# Board_lengkap.net
KiCad netlist of a schematic drawn in EAGLE
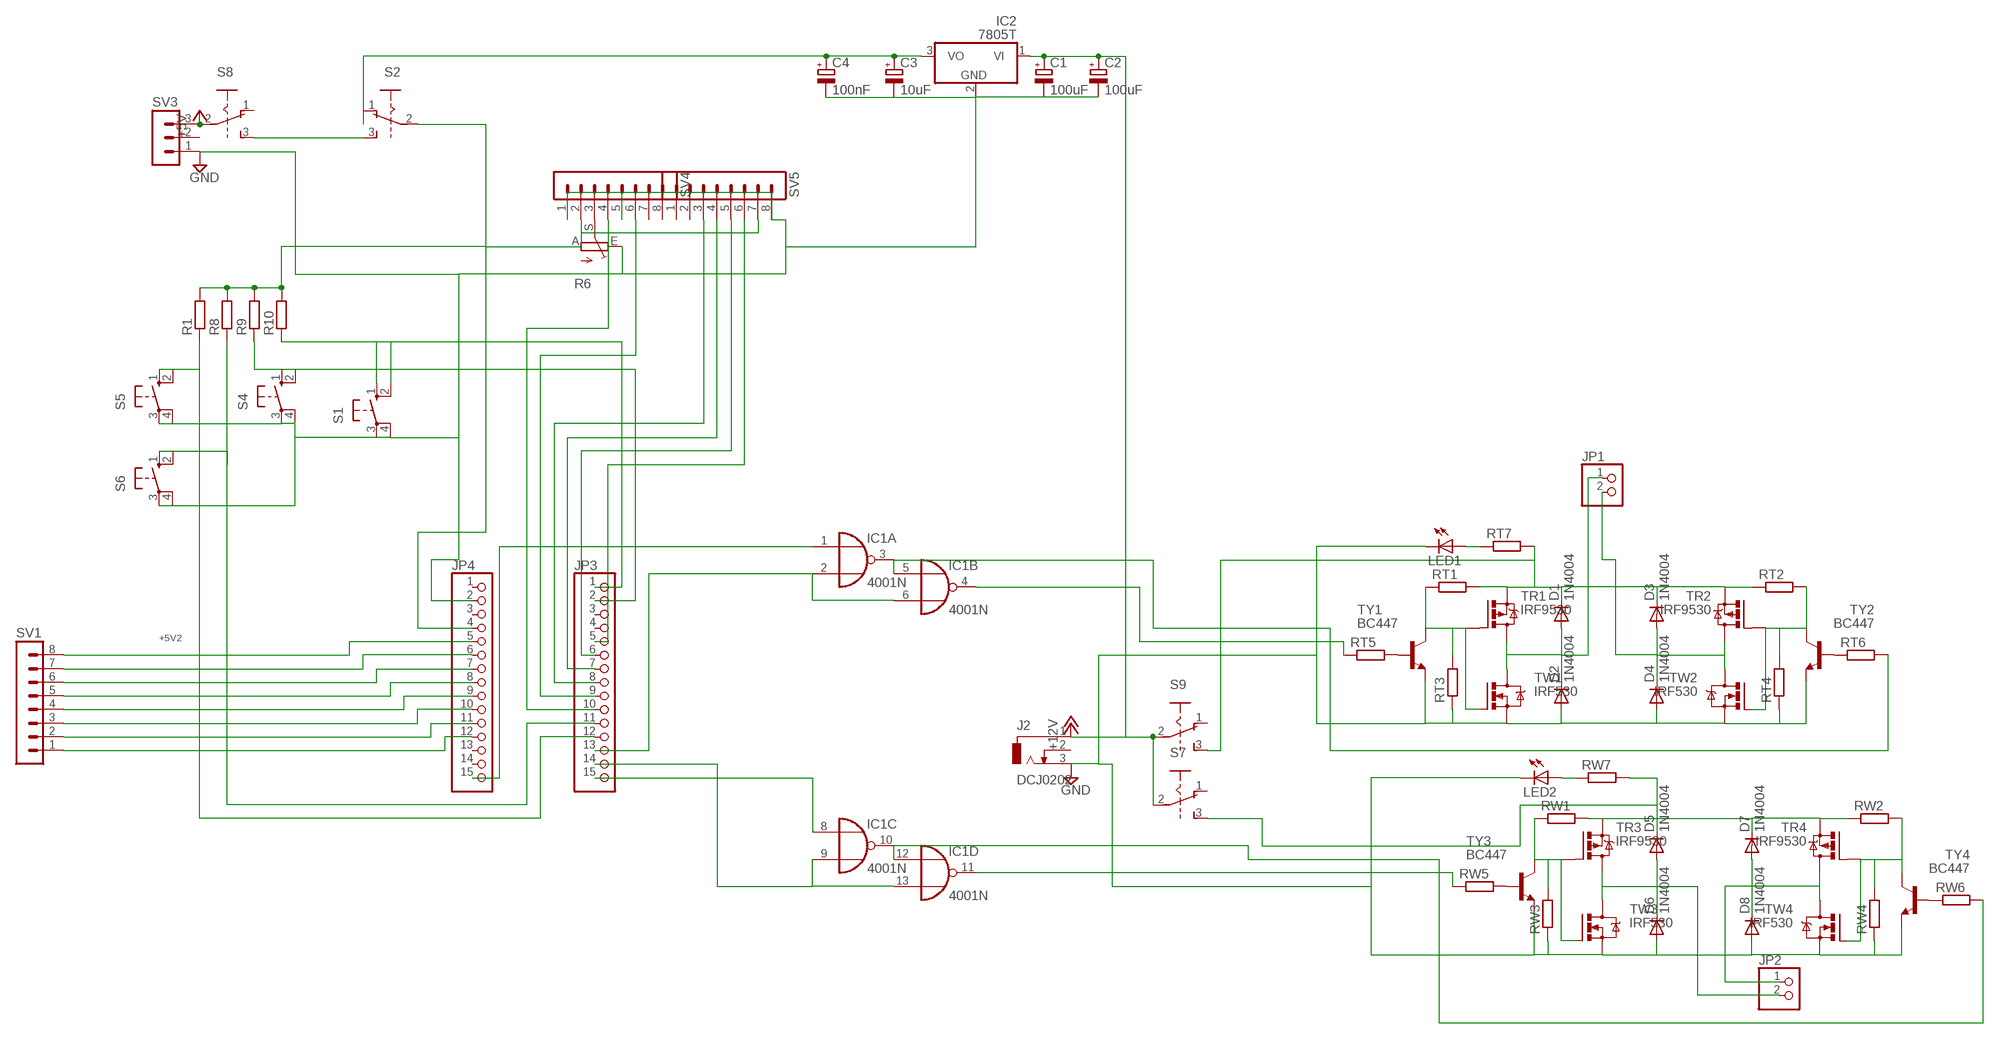
[diagram p0: schematic, sheet 1]
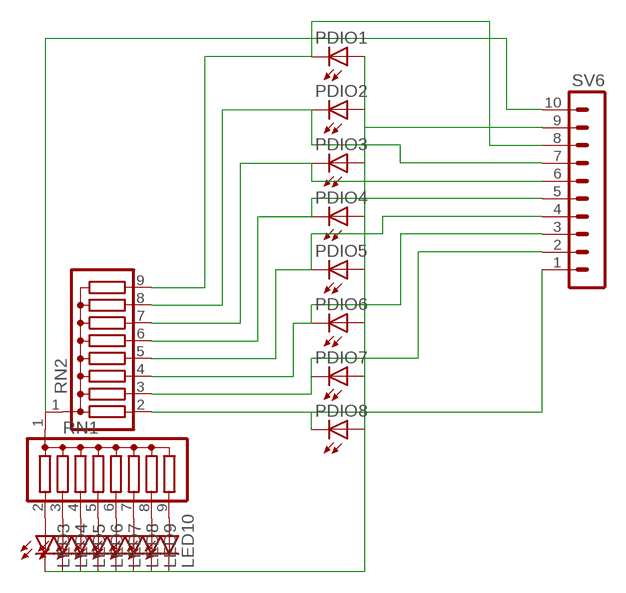
[diagram p1: schematic, sheet 2]

(export (version "E")
  (design (tool "Eeschema 10.0.6"))
  (components
    (comp (ref "LED3")
      (value "LED3MM")
      (footprint "eagle-import:LED3MM")
      (libsource (lib "eagle-import") (part "LED3MM"))
    )
    (comp (ref "LED4")
      (value "LED3MM")
      (footprint "eagle-import:LED3MM")
      (libsource (lib "eagle-import") (part "LED3MM"))
    )
    (comp (ref "LED5")
      (value "LED3MM")
      (footprint "eagle-import:LED3MM")
      (libsource (lib "eagle-import") (part "LED3MM"))
    )
    (comp (ref "LED6")
      (value "LED3MM")
      (footprint "eagle-import:LED3MM")
      (libsource (lib "eagle-import") (part "LED3MM"))
    )
    (comp (ref "LED7")
      (value "LED3MM")
      (footprint "eagle-import:LED3MM")
      (libsource (lib "eagle-import") (part "LED3MM"))
    )
    (comp (ref "LED8")
      (value "LED3MM")
      (footprint "eagle-import:LED3MM")
      (libsource (lib "eagle-import") (part "LED3MM"))
    )
    (comp (ref "LED9")
      (value "LED3MM")
      (footprint "eagle-import:LED3MM")
      (libsource (lib "eagle-import") (part "LED3MM"))
    )
    (comp (ref "LED10")
      (value "LED3MM")
      (footprint "eagle-import:LED3MM")
      (libsource (lib "eagle-import") (part "LED3MM"))
    )
    (comp (ref "PDIO1")
      (value "LED3MM")
      (footprint "eagle-import:LED3MM")
      (libsource (lib "eagle-import") (part "LED3MM"))
    )
    (comp (ref "PDIO2")
      (value "LED3MM")
      (footprint "eagle-import:LED3MM")
      (libsource (lib "eagle-import") (part "LED3MM"))
    )
    (comp (ref "PDIO3")
      (value "LED3MM")
      (footprint "eagle-import:LED3MM")
      (libsource (lib "eagle-import") (part "LED3MM"))
    )
    (comp (ref "PDIO4")
      (value "LED3MM")
      (footprint "eagle-import:LED3MM")
      (libsource (lib "eagle-import") (part "LED3MM"))
    )
    (comp (ref "PDIO5")
      (value "LED3MM")
      (footprint "eagle-import:LED3MM")
      (libsource (lib "eagle-import") (part "LED3MM"))
    )
    (comp (ref "PDIO6")
      (value "LED3MM")
      (footprint "eagle-import:LED3MM")
      (libsource (lib "eagle-import") (part "LED3MM"))
    )
    (comp (ref "PDIO7")
      (value "LED3MM")
      (footprint "eagle-import:LED3MM")
      (libsource (lib "eagle-import") (part "LED3MM"))
    )
    (comp (ref "PDIO8")
      (value "LED3MM")
      (footprint "eagle-import:LED3MM")
      (libsource (lib "eagle-import") (part "LED3MM"))
    )
    (comp (ref "RN1")
      (value "G08R")
      (footprint "eagle-import:SIL9")
      (libsource (lib "eagle-import") (part "G08R"))
    )
    (comp (ref "RN2")
      (value "G08R")
      (footprint "eagle-import:SIL9")
      (libsource (lib "eagle-import") (part "G08R"))
    )
    (comp (ref "SV6")
      (value "MA10-1")
      (footprint "eagle-import:MA10-1")
      (libsource (lib "eagle-import") (part "MA10-1"))
    )
    (comp (ref "C1")
      (value "100uF")
      (footprint "eagle-import:E2,5-6")
      (libsource (lib "eagle-import") (part "CPOL-EUE2.5-6"))
    )
    (comp (ref "C2")
      (value "100uF")
      (footprint "eagle-import:E2,5-6")
      (libsource (lib "eagle-import") (part "CPOL-EUE2.5-6"))
    )
    (comp (ref "C3")
      (value "10uF")
      (footprint "eagle-import:E2,5-6")
      (libsource (lib "eagle-import") (part "CPOL-EUE2.5-6"))
    )
    (comp (ref "C4")
      (value "100nF")
      (footprint "eagle-import:E2,5-6")
      (libsource (lib "eagle-import") (part "CPOL-EUE2.5-6"))
    )
    (comp (ref "D1")
      (value "1N4004")
      (footprint "eagle-import:DO41-10")
      (libsource (lib "eagle-import") (part "1N4004"))
    )
    (comp (ref "D2")
      (value "1N4004")
      (footprint "eagle-import:DO41-10")
      (libsource (lib "eagle-import") (part "1N4004"))
    )
    (comp (ref "D3")
      (value "1N4004")
      (footprint "eagle-import:DO41-10")
      (libsource (lib "eagle-import") (part "1N4004"))
    )
    (comp (ref "D4")
      (value "1N4004")
      (footprint "eagle-import:DO41-10")
      (libsource (lib "eagle-import") (part "1N4004"))
    )
    (comp (ref "D5")
      (value "1N4004")
      (footprint "eagle-import:DO41-10")
      (libsource (lib "eagle-import") (part "1N4004"))
    )
    (comp (ref "D6")
      (value "1N4004")
      (footprint "eagle-import:DO41-10")
      (libsource (lib "eagle-import") (part "1N4004"))
    )
    (comp (ref "D7")
      (value "1N4004")
      (footprint "eagle-import:DO41-10")
      (libsource (lib "eagle-import") (part "1N4004"))
    )
    (comp (ref "D8")
      (value "1N4004")
      (footprint "eagle-import:DO41-10")
      (libsource (lib "eagle-import") (part "1N4004"))
    )
    (comp (ref "IC1")
      (value "4001N")
      (footprint "eagle-import:DIL14")
      (libsource (lib "eagle-import") (part "4001N"))
    )
    (comp (ref "IC2")
      (value "7805T")
      (footprint "eagle-import:TO220H")
      (libsource (lib "eagle-import") (part "78T05"))
    )
    (comp (ref "J2")
      (value "DCJ0202")
      (footprint "eagle-import:DCJ0202")
      (libsource (lib "eagle-import") (part "DCJ0202"))
    )
    (comp (ref "JP1")
      (value "PINHD-1X2")
      (footprint "eagle-import:1X02")
      (libsource (lib "eagle-import") (part "PINHD-1X2"))
    )
    (comp (ref "JP2")
      (value "PINHD-1X2")
      (footprint "eagle-import:1X02")
      (libsource (lib "eagle-import") (part "PINHD-1X2"))
    )
    (comp (ref "JP3")
      (value "PINHD-1X15")
      (footprint "eagle-import:1X15")
      (libsource (lib "eagle-import") (part "PINHD-1X15"))
    )
    (comp (ref "JP4")
      (value "PINHD-1X15")
      (footprint "eagle-import:1X15")
      (libsource (lib "eagle-import") (part "PINHD-1X15"))
    )
    (comp (ref "LED1")
      (value "LED5MM")
      (footprint "eagle-import:LED5MM")
      (libsource (lib "eagle-import") (part "LED5MM"))
    )
    (comp (ref "LED2")
      (value "LED5MM")
      (footprint "eagle-import:LED5MM")
      (libsource (lib "eagle-import") (part "LED5MM"))
    )
    (comp (ref "R1")
      (value "R-EU_0204/7")
      (footprint "eagle-import:0204_7")
      (libsource (lib "eagle-import") (part "R-EU_0204/7"))
    )
    (comp (ref "R6")
      (value "TRIM_EU-B25P")
      (footprint "eagle-import:B25P")
      (libsource (lib "eagle-import") (part "TRIM_EU-B25P"))
    )
    (comp (ref "R8")
      (value "R-EU_0204/7")
      (footprint "eagle-import:0204_7")
      (libsource (lib "eagle-import") (part "R-EU_0204/7"))
    )
    (comp (ref "R9")
      (value "R-EU_0204/7")
      (footprint "eagle-import:0204_7")
      (libsource (lib "eagle-import") (part "R-EU_0204/7"))
    )
    (comp (ref "R10")
      (value "R-EU_0204/7")
      (footprint "eagle-import:0204_7")
      (libsource (lib "eagle-import") (part "R-EU_0204/7"))
    )
    (comp (ref "RT1")
      (value "R-EU_0207/7")
      (footprint "eagle-import:0207_7")
      (libsource (lib "eagle-import") (part "R-EU_0207/7"))
    )
    (comp (ref "RT2")
      (value "R-EU_0207/7")
      (footprint "eagle-import:0207_7")
      (libsource (lib "eagle-import") (part "R-EU_0207/7"))
    )
    (comp (ref "RT3")
      (value "R-EU_0207/7")
      (footprint "eagle-import:0207_7")
      (libsource (lib "eagle-import") (part "R-EU_0207/7"))
    )
    (comp (ref "RT4")
      (value "R-EU_0207/7")
      (footprint "eagle-import:0207_7")
      (libsource (lib "eagle-import") (part "R-EU_0207/7"))
    )
    (comp (ref "RT5")
      (value "R-EU_0207/7")
      (footprint "eagle-import:0207_7")
      (libsource (lib "eagle-import") (part "R-EU_0207/7"))
    )
    (comp (ref "RT6")
      (value "R-EU_0207/7")
      (footprint "eagle-import:0207_7")
      (libsource (lib "eagle-import") (part "R-EU_0207/7"))
    )
    (comp (ref "RT7")
      (value "R-EU_0207/7")
      (footprint "eagle-import:0207_7")
      (libsource (lib "eagle-import") (part "R-EU_0207/7"))
    )
    (comp (ref "RW1")
      (value "R-EU_0207/7")
      (footprint "eagle-import:0207_7")
      (libsource (lib "eagle-import") (part "R-EU_0207/7"))
    )
    (comp (ref "RW2")
      (value "R-EU_0207/7")
      (footprint "eagle-import:0207_7")
      (libsource (lib "eagle-import") (part "R-EU_0207/7"))
    )
    (comp (ref "RW3")
      (value "R-EU_0207/7")
      (footprint "eagle-import:0207_7")
      (libsource (lib "eagle-import") (part "R-EU_0207/7"))
    )
    (comp (ref "RW4")
      (value "R-EU_0207/7")
      (footprint "eagle-import:0207_7")
      (libsource (lib "eagle-import") (part "R-EU_0207/7"))
    )
    (comp (ref "RW5")
      (value "R-EU_0207/7")
      (footprint "eagle-import:0207_7")
      (libsource (lib "eagle-import") (part "R-EU_0207/7"))
    )
    (comp (ref "RW6")
      (value "R-EU_0207/7")
      (footprint "eagle-import:0207_7")
      (libsource (lib "eagle-import") (part "R-EU_0207/7"))
    )
    (comp (ref "RW7")
      (value "R-EU_0207/7")
      (footprint "eagle-import:0207_7")
      (libsource (lib "eagle-import") (part "R-EU_0207/7"))
    )
    (comp (ref "S1")
      (value "10-XX")
      (footprint "eagle-import:B3F-10XX")
      (libsource (lib "eagle-import") (part "10-XX"))
    )
    (comp (ref "S2")
      (value "A68-A31")
      (footprint "eagle-import:A68-A31")
      (libsource (lib "eagle-import") (part "A68-A31"))
    )
    (comp (ref "S4")
      (value "10-XX")
      (footprint "eagle-import:B3F-10XX")
      (libsource (lib "eagle-import") (part "10-XX"))
    )
    (comp (ref "S5")
      (value "10-XX")
      (footprint "eagle-import:B3F-10XX")
      (libsource (lib "eagle-import") (part "10-XX"))
    )
    (comp (ref "S6")
      (value "10-XX")
      (footprint "eagle-import:B3F-10XX")
      (libsource (lib "eagle-import") (part "10-XX"))
    )
    (comp (ref "S7")
      (value "A68-A31")
      (footprint "eagle-import:A68-A31")
      (libsource (lib "eagle-import") (part "A68-A31"))
    )
    (comp (ref "S8")
      (value "A68-A31")
      (footprint "eagle-import:A68-A31")
      (libsource (lib "eagle-import") (part "A68-A31"))
    )
    (comp (ref "S9")
      (value "A68-A31")
      (footprint "eagle-import:A68-A31")
      (libsource (lib "eagle-import") (part "A68-A31"))
    )
    (comp (ref "SV1")
      (value "MA08-1")
      (footprint "eagle-import:MA08-1")
      (libsource (lib "eagle-import") (part "MA08-1"))
    )
    (comp (ref "SV3")
      (value "MA03-1")
      (footprint "eagle-import:MA03-1")
      (libsource (lib "eagle-import") (part "MA03-1"))
    )
    (comp (ref "SV4")
      (value "MA08-1")
      (footprint "eagle-import:MA08-1")
      (libsource (lib "eagle-import") (part "MA08-1"))
    )
    (comp (ref "SV5")
      (value "MA08-1")
      (footprint "eagle-import:MA08-1")
      (libsource (lib "eagle-import") (part "MA08-1"))
    )
    (comp (ref "TR1")
      (value "IRF9530")
      (footprint "eagle-import:TO220BV")
      (libsource (lib "eagle-import") (part "IRF9530"))
    )
    (comp (ref "TR2")
      (value "IRF9530")
      (footprint "eagle-import:TO220BV")
      (libsource (lib "eagle-import") (part "IRF9530"))
    )
    (comp (ref "TR3")
      (value "IRF9530")
      (footprint "eagle-import:TO220BV")
      (libsource (lib "eagle-import") (part "IRF9530"))
    )
    (comp (ref "TR4")
      (value "IRF9530")
      (footprint "eagle-import:TO220BV")
      (libsource (lib "eagle-import") (part "IRF9530"))
    )
    (comp (ref "TW1")
      (value "IRF530")
      (footprint "eagle-import:TO220BV")
      (libsource (lib "eagle-import") (part "IRF530"))
    )
    (comp (ref "TW2")
      (value "IRF530")
      (footprint "eagle-import:TO220BV")
      (libsource (lib "eagle-import") (part "IRF530"))
    )
    (comp (ref "TW3")
      (value "IRF530")
      (footprint "eagle-import:TO220BV")
      (libsource (lib "eagle-import") (part "IRF530"))
    )
    (comp (ref "TW4")
      (value "IRF530")
      (footprint "eagle-import:TO220BV")
      (libsource (lib "eagle-import") (part "IRF530"))
    )
    (comp (ref "TY1")
      (value "BC447")
      (footprint "eagle-import:TO92-EBC")
      (libsource (lib "eagle-import") (part "BC447"))
    )
    (comp (ref "TY2")
      (value "BC447")
      (footprint "eagle-import:TO92-EBC")
      (libsource (lib "eagle-import") (part "BC447"))
    )
    (comp (ref "TY3")
      (value "BC447")
      (footprint "eagle-import:TO92-EBC")
      (libsource (lib "eagle-import") (part "BC447"))
    )
    (comp (ref "TY4")
      (value "BC447")
      (footprint "eagle-import:TO92-EBC")
      (libsource (lib "eagle-import") (part "BC447"))
    )
  )
  (nets
    (net (code "1") (name "+5V") (class "Default")
      (node (ref "S8") (pin "2") (pinfunction "P_2") (pintype "passive"))
      (node (ref "SV3") (pin "3") (pinfunction "3_3") (pintype "passive"))
    )
    (net (code "2") (name "+5V2") (class "Default")
      (node (ref "JP4") (pin "4") (pinfunction "4_4") (pintype "passive"))
      (node (ref "R1") (pin "2") (pinfunction "2_2") (pintype "passive"))
      (node (ref "R10") (pin "2") (pinfunction "2_2") (pintype "passive"))
      (node (ref "R6") (pin "A") (pinfunction "A_A") (pintype "passive"))
      (node (ref "R8") (pin "2") (pinfunction "2_2") (pintype "passive"))
      (node (ref "R9") (pin "2") (pinfunction "2_2") (pintype "passive"))
      (node (ref "S2") (pin "2") (pinfunction "P_2") (pintype "passive"))
      (node (ref "SV4") (pin "2") (pinfunction "2_2") (pintype "passive"))
      (node (ref "SV5") (pin "7") (pinfunction "7_7") (pintype "passive"))
    )
    (net (code "3") (name "+12V") (class "Default")
      (node (ref "C1") (pin "+") (pinfunction "+_+") (pintype "passive"))
      (node (ref "C2") (pin "+") (pinfunction "+_+") (pintype "passive"))
      (node (ref "IC2") (pin "1") (pinfunction "VI_1") (pintype "input"))
      (node (ref "J2") (pin "1") (pinfunction "1_1") (pintype "passive"))
      (node (ref "S7") (pin "2") (pinfunction "P_2") (pintype "passive"))
      (node (ref "S9") (pin "2") (pinfunction "P_2") (pintype "passive"))
    )
    (net (code "4") (name "GND") (class "Default")
      (node (ref "C1") (pin "-") (pinfunction "-_-") (pintype "passive"))
      (node (ref "C2") (pin "-") (pinfunction "-_-") (pintype "passive"))
      (node (ref "C3") (pin "-") (pinfunction "-_-") (pintype "passive"))
      (node (ref "C4") (pin "-") (pinfunction "-_-") (pintype "passive"))
      (node (ref "D2") (pin "A") (pinfunction "A_A") (pintype "passive"))
      (node (ref "D4") (pin "A") (pinfunction "A_A") (pintype "passive"))
      (node (ref "D6") (pin "A") (pinfunction "A_A") (pintype "passive"))
      (node (ref "D8") (pin "A") (pinfunction "A_A") (pintype "passive"))
      (node (ref "IC2") (pin "2") (pinfunction "GND_2") (pintype "passive"))
      (node (ref "J2") (pin "3") (pinfunction "3_3") (pintype "passive"))
      (node (ref "JP4") (pin "2") (pinfunction "2_2") (pintype "passive"))
      (node (ref "LED1") (pin "K") (pinfunction "C_K") (pintype "passive"))
      (node (ref "LED2") (pin "K") (pinfunction "C_K") (pintype "passive"))
      (node (ref "R6") (pin "E") (pinfunction "E_E") (pintype "passive"))
      (node (ref "RT3") (pin "1") (pinfunction "1_1") (pintype "passive"))
      (node (ref "RT4") (pin "1") (pinfunction "1_1") (pintype "passive"))
      (node (ref "RW3") (pin "1") (pinfunction "1_1") (pintype "passive"))
      (node (ref "RW4") (pin "1") (pinfunction "1_1") (pintype "passive"))
      (node (ref "S1") (pin "3") (pinfunction "P_3") (pintype "passive"))
      (node (ref "S1") (pin "4") (pinfunction "P1_4") (pintype "passive"))
      (node (ref "S4") (pin "3") (pinfunction "P_3") (pintype "passive"))
      (node (ref "S4") (pin "4") (pinfunction "P1_4") (pintype "passive"))
      (node (ref "S5") (pin "3") (pinfunction "P_3") (pintype "passive"))
      (node (ref "S5") (pin "4") (pinfunction "P1_4") (pintype "passive"))
      (node (ref "S6") (pin "3") (pinfunction "P_3") (pintype "passive"))
      (node (ref "S6") (pin "4") (pinfunction "P1_4") (pintype "passive"))
      (node (ref "SV3") (pin "1") (pinfunction "1_1") (pintype "passive"))
      (node (ref "SV4") (pin "1") (pinfunction "1_1") (pintype "passive"))
      (node (ref "SV4") (pin "5") (pinfunction "5_5") (pintype "passive"))
      (node (ref "SV5") (pin "8") (pinfunction "8_8") (pintype "passive"))
      (node (ref "TW1") (pin "S") (pinfunction "S_S") (pintype "passive"))
      (node (ref "TW2") (pin "S") (pinfunction "S_S") (pintype "passive"))
      (node (ref "TW3") (pin "S") (pinfunction "S_S") (pintype "passive"))
      (node (ref "TW4") (pin "S") (pinfunction "S_S") (pintype "passive"))
      (node (ref "TY1") (pin "E") (pinfunction "E_E") (pintype "passive"))
      (node (ref "TY2") (pin "E") (pinfunction "E_E") (pintype "passive"))
      (node (ref "TY3") (pin "E") (pinfunction "E_E") (pintype "passive"))
      (node (ref "TY4") (pin "E") (pinfunction "E_E") (pintype "passive"))
    )
    (net (code "5") (name "Net-(D1-PadA)") (class "Default")
      (node (ref "D1") (pin "A") (pinfunction "A_A") (pintype "passive"))
      (node (ref "D2") (pin "C") (pinfunction "C_C") (pintype "passive"))
      (node (ref "JP1") (pin "1") (pinfunction "1_1") (pintype "passive"))
      (node (ref "TR1") (pin "D") (pinfunction "D_D") (pintype "passive"))
      (node (ref "TW1") (pin "D") (pinfunction "D_D") (pintype "passive"))
    )
    (net (code "6") (name "Net-(D3-PadA)") (class "Default")
      (node (ref "D3") (pin "A") (pinfunction "A_A") (pintype "passive"))
      (node (ref "D4") (pin "C") (pinfunction "C_C") (pintype "passive"))
      (node (ref "JP1") (pin "2") (pinfunction "2_2") (pintype "passive"))
      (node (ref "TR2") (pin "D") (pinfunction "D_D") (pintype "passive"))
      (node (ref "TW2") (pin "D") (pinfunction "D_D") (pintype "passive"))
    )
    (net (code "7") (name "Net-(D5-PadA)") (class "Default")
      (node (ref "D5") (pin "A") (pinfunction "A_A") (pintype "passive"))
      (node (ref "D6") (pin "C") (pinfunction "C_C") (pintype "passive"))
      (node (ref "JP2") (pin "2") (pinfunction "2_2") (pintype "passive"))
      (node (ref "TR3") (pin "D") (pinfunction "D_D") (pintype "passive"))
      (node (ref "TW3") (pin "D") (pinfunction "D_D") (pintype "passive"))
    )
    (net (code "8") (name "Net-(D7-PadA)") (class "Default")
      (node (ref "D7") (pin "A") (pinfunction "A_A") (pintype "passive"))
      (node (ref "D8") (pin "C") (pinfunction "C_C") (pintype "passive"))
      (node (ref "JP2") (pin "1") (pinfunction "1_1") (pintype "passive"))
      (node (ref "TR4") (pin "D") (pinfunction "D_D") (pintype "passive"))
      (node (ref "TW4") (pin "D") (pinfunction "D_D") (pintype "passive"))
    )
    (net (code "9") (name "Net-(IC1A-I0)") (class "Default")
      (node (ref "IC1") (pin "1") (pinfunction "I0_1") (pintype "input"))
      (node (ref "JP4") (pin "15") (pinfunction "15_15") (pintype "passive"))
    )
    (net (code "10") (name "Net-(IC1A-I1)") (class "Default")
      (node (ref "IC1") (pin "2") (pinfunction "I1_2") (pintype "input"))
      (node (ref "IC1") (pin "6") (pinfunction "I1_6") (pintype "input"))
      (node (ref "JP3") (pin "13") (pinfunction "13_13") (pintype "passive"))
    )
    (net (code "11") (name "Net-(IC1A-O)") (class "Default")
      (node (ref "IC1") (pin "3") (pinfunction "O_3") (pintype "output"))
      (node (ref "IC1") (pin "5") (pinfunction "I0_5") (pintype "input"))
      (node (ref "RT6") (pin "2") (pinfunction "2_2") (pintype "passive"))
    )
    (net (code "12") (name "Net-(IC1B-O)") (class "Default")
      (node (ref "IC1") (pin "4") (pinfunction "O_4") (pintype "output"))
      (node (ref "RT5") (pin "1") (pinfunction "1_1") (pintype "passive"))
    )
    (net (code "13") (name "Net-(IC1C-I0)") (class "Default")
      (node (ref "IC1") (pin "8") (pinfunction "I0_8") (pintype "input"))
      (node (ref "JP3") (pin "15") (pinfunction "15_15") (pintype "passive"))
    )
    (net (code "14") (name "Net-(IC1C-I1)") (class "Default")
      (node (ref "IC1") (pin "13") (pinfunction "I1_13") (pintype "input"))
      (node (ref "IC1") (pin "9") (pinfunction "I1_9") (pintype "input"))
      (node (ref "JP3") (pin "14") (pinfunction "14_14") (pintype "passive"))
    )
    (net (code "15") (name "Net-(IC1C-O)") (class "Default")
      (node (ref "IC1") (pin "10") (pinfunction "O_10") (pintype "output"))
      (node (ref "IC1") (pin "12") (pinfunction "I0_12") (pintype "input"))
      (node (ref "RW6") (pin "2") (pinfunction "2_2") (pintype "passive"))
    )
    (net (code "16") (name "Net-(IC1D-O)") (class "Default")
      (node (ref "IC1") (pin "11") (pinfunction "O_11") (pintype "output"))
      (node (ref "RW5") (pin "1") (pinfunction "1_1") (pintype "passive"))
    )
    (net (code "17") (name "Net-(IC2-VO)") (class "Default")
      (node (ref "C3") (pin "+") (pinfunction "+_+") (pintype "passive"))
      (node (ref "C4") (pin "+") (pinfunction "+_+") (pintype "passive"))
      (node (ref "IC2") (pin "3") (pinfunction "VO_3") (pintype "passive"))
    )
    (net (code "18") (name "Net-(JP3-Pad5)") (class "Default")
      (node (ref "JP3") (pin "5") (pinfunction "5_5") (pintype "passive"))
      (node (ref "SV5") (pin "6") (pinfunction "6_6") (pintype "passive"))
    )
    (net (code "19") (name "Net-(JP3-Pad6)") (class "Default")
      (node (ref "JP3") (pin "6") (pinfunction "6_6") (pintype "passive"))
      (node (ref "SV5") (pin "5") (pinfunction "5_5") (pintype "passive"))
    )
    (net (code "20") (name "Net-(JP3-Pad7)") (class "Default")
      (node (ref "JP3") (pin "7") (pinfunction "7_7") (pintype "passive"))
      (node (ref "SV5") (pin "4") (pinfunction "4_4") (pintype "passive"))
    )
    (net (code "21") (name "Net-(JP3-Pad8)") (class "Default")
      (node (ref "JP3") (pin "8") (pinfunction "8_8") (pintype "passive"))
      (node (ref "SV5") (pin "3") (pinfunction "3_3") (pintype "passive"))
    )
    (net (code "22") (name "Net-(JP3-Pad9)") (class "Default")
      (node (ref "JP3") (pin "9") (pinfunction "9_9") (pintype "passive"))
      (node (ref "SV4") (pin "6") (pinfunction "6_6") (pintype "passive"))
    )
    (net (code "23") (name "Net-(JP3-Pad10)") (class "Default")
      (node (ref "JP3") (pin "10") (pinfunction "10_10") (pintype "passive"))
      (node (ref "SV4") (pin "4") (pinfunction "4_4") (pintype "passive"))
    )
    (net (code "24") (name "Net-(JP4-Pad5)") (class "Default")
      (node (ref "JP4") (pin "5") (pinfunction "5_5") (pintype "passive"))
      (node (ref "SV1") (pin "8") (pinfunction "8_8") (pintype "passive"))
    )
    (net (code "25") (name "Net-(JP4-Pad6)") (class "Default")
      (node (ref "JP4") (pin "6") (pinfunction "6_6") (pintype "passive"))
      (node (ref "SV1") (pin "7") (pinfunction "7_7") (pintype "passive"))
    )
    (net (code "26") (name "Net-(JP4-Pad7)") (class "Default")
      (node (ref "JP4") (pin "7") (pinfunction "7_7") (pintype "passive"))
      (node (ref "SV1") (pin "6") (pinfunction "6_6") (pintype "passive"))
    )
    (net (code "27") (name "Net-(JP4-Pad8)") (class "Default")
      (node (ref "JP4") (pin "8") (pinfunction "8_8") (pintype "passive"))
      (node (ref "SV1") (pin "5") (pinfunction "5_5") (pintype "passive"))
    )
    (net (code "28") (name "Net-(JP4-Pad9)") (class "Default")
      (node (ref "JP4") (pin "9") (pinfunction "9_9") (pintype "passive"))
      (node (ref "SV1") (pin "4") (pinfunction "4_4") (pintype "passive"))
    )
    (net (code "29") (name "Net-(JP4-Pad10)") (class "Default")
      (node (ref "JP4") (pin "10") (pinfunction "10_10") (pintype "passive"))
      (node (ref "SV1") (pin "3") (pinfunction "3_3") (pintype "passive"))
    )
    (net (code "30") (name "Net-(JP4-Pad11)") (class "Default")
      (node (ref "JP4") (pin "11") (pinfunction "11_11") (pintype "passive"))
      (node (ref "SV1") (pin "2") (pinfunction "2_2") (pintype "passive"))
    )
    (net (code "31") (name "Net-(JP4-Pad12)") (class "Default")
      (node (ref "JP4") (pin "12") (pinfunction "12_12") (pintype "passive"))
      (node (ref "SV1") (pin "1") (pinfunction "1_1") (pintype "passive"))
    )
    (net (code "32") (name "Net-(LED1-PadA)") (class "Default")
      (node (ref "LED1") (pin "A") (pinfunction "A_A") (pintype "passive"))
      (node (ref "RT7") (pin "1") (pinfunction "1_1") (pintype "passive"))
    )
    (net (code "33") (name "Net-(LED2-PadA)") (class "Default")
      (node (ref "LED2") (pin "A") (pinfunction "A_A") (pintype "passive"))
      (node (ref "RW7") (pin "1") (pinfunction "1_1") (pintype "passive"))
    )
    (net (code "34") (name "Net-(LED3-PadA)") (class "Default")
      (node (ref "LED3") (pin "A") (pinfunction "A_A") (pintype "passive"))
      (node (ref "RN1") (pin "2") (pinfunction "2_2") (pintype "passive"))
    )
    (net (code "35") (name "Net-(LED4-PadA)") (class "Default")
      (node (ref "LED4") (pin "A") (pinfunction "A_A") (pintype "passive"))
      (node (ref "RN1") (pin "3") (pinfunction "3_3") (pintype "passive"))
    )
    (net (code "36") (name "Net-(LED5-PadA)") (class "Default")
      (node (ref "LED5") (pin "A") (pinfunction "A_A") (pintype "passive"))
      (node (ref "RN1") (pin "4") (pinfunction "4_4") (pintype "passive"))
    )
    (net (code "37") (name "Net-(LED6-PadA)") (class "Default")
      (node (ref "LED6") (pin "A") (pinfunction "A_A") (pintype "passive"))
      (node (ref "RN1") (pin "5") (pinfunction "5_5") (pintype "passive"))
    )
    (net (code "38") (name "Net-(LED7-PadA)") (class "Default")
      (node (ref "LED7") (pin "A") (pinfunction "A_A") (pintype "passive"))
      (node (ref "RN1") (pin "6") (pinfunction "6_6") (pintype "passive"))
    )
    (net (code "39") (name "Net-(LED8-PadA)") (class "Default")
      (node (ref "LED8") (pin "A") (pinfunction "A_A") (pintype "passive"))
      (node (ref "RN1") (pin "7") (pinfunction "7_7") (pintype "passive"))
    )
    (net (code "40") (name "Net-(LED9-PadA)") (class "Default")
      (node (ref "LED9") (pin "A") (pinfunction "A_A") (pintype "passive"))
      (node (ref "RN1") (pin "8") (pinfunction "8_8") (pintype "passive"))
    )
    (net (code "41") (name "Net-(LED10-C)") (class "Default")
      (node (ref "LED10") (pin "K") (pinfunction "C_K") (pintype "passive"))
      (node (ref "LED3") (pin "K") (pinfunction "C_K") (pintype "passive"))
      (node (ref "LED4") (pin "K") (pinfunction "C_K") (pintype "passive"))
      (node (ref "LED5") (pin "K") (pinfunction "C_K") (pintype "passive"))
      (node (ref "LED6") (pin "K") (pinfunction "C_K") (pintype "passive"))
      (node (ref "LED7") (pin "K") (pinfunction "C_K") (pintype "passive"))
      (node (ref "LED8") (pin "K") (pinfunction "C_K") (pintype "passive"))
      (node (ref "LED9") (pin "K") (pinfunction "C_K") (pintype "passive"))
      (node (ref "PDIO1") (pin "A") (pinfunction "A_A") (pintype "passive"))
      (node (ref "PDIO2") (pin "A") (pinfunction "A_A") (pintype "passive"))
      (node (ref "PDIO3") (pin "A") (pinfunction "A_A") (pintype "passive"))
      (node (ref "PDIO4") (pin "A") (pinfunction "A_A") (pintype "passive"))
      (node (ref "PDIO5") (pin "A") (pinfunction "A_A") (pintype "passive"))
      (node (ref "PDIO6") (pin "A") (pinfunction "A_A") (pintype "passive"))
      (node (ref "PDIO7") (pin "A") (pinfunction "A_A") (pintype "passive"))
      (node (ref "PDIO8") (pin "A") (pinfunction "A_A") (pintype "passive"))
      (node (ref "SV6") (pin "9") (pinfunction "9_9") (pintype "passive"))
    )
    (net (code "42") (name "Net-(LED10-PadA)") (class "Default")
      (node (ref "LED10") (pin "A") (pinfunction "A_A") (pintype "passive"))
      (node (ref "RN1") (pin "9") (pinfunction "9_9") (pintype "passive"))
    )
    (net (code "43") (name "Net-(PDIO1-C)") (class "Default")
      (node (ref "PDIO1") (pin "K") (pinfunction "C_K") (pintype "passive"))
      (node (ref "RN2") (pin "9") (pinfunction "9_9") (pintype "passive"))
      (node (ref "SV6") (pin "8") (pinfunction "8_8") (pintype "passive"))
    )
    (net (code "44") (name "Net-(PDIO2-C)") (class "Default")
      (node (ref "PDIO2") (pin "K") (pinfunction "C_K") (pintype "passive"))
      (node (ref "RN2") (pin "8") (pinfunction "8_8") (pintype "passive"))
      (node (ref "SV6") (pin "7") (pinfunction "7_7") (pintype "passive"))
    )
    (net (code "45") (name "Net-(PDIO3-C)") (class "Default")
      (node (ref "PDIO3") (pin "K") (pinfunction "C_K") (pintype "passive"))
      (node (ref "RN2") (pin "7") (pinfunction "7_7") (pintype "passive"))
      (node (ref "SV6") (pin "6") (pinfunction "6_6") (pintype "passive"))
    )
    (net (code "46") (name "Net-(PDIO4-C)") (class "Default")
      (node (ref "PDIO4") (pin "K") (pinfunction "C_K") (pintype "passive"))
      (node (ref "RN2") (pin "6") (pinfunction "6_6") (pintype "passive"))
      (node (ref "SV6") (pin "5") (pinfunction "5_5") (pintype "passive"))
    )
    (net (code "47") (name "Net-(PDIO5-C)") (class "Default")
      (node (ref "PDIO5") (pin "K") (pinfunction "C_K") (pintype "passive"))
      (node (ref "RN2") (pin "5") (pinfunction "5_5") (pintype "passive"))
      (node (ref "SV6") (pin "4") (pinfunction "4_4") (pintype "passive"))
    )
    (net (code "48") (name "Net-(PDIO6-C)") (class "Default")
      (node (ref "PDIO6") (pin "K") (pinfunction "C_K") (pintype "passive"))
      (node (ref "RN2") (pin "4") (pinfunction "4_4") (pintype "passive"))
      (node (ref "SV6") (pin "3") (pinfunction "3_3") (pintype "passive"))
    )
    (net (code "49") (name "Net-(PDIO7-C)") (class "Default")
      (node (ref "PDIO7") (pin "K") (pinfunction "C_K") (pintype "passive"))
      (node (ref "RN2") (pin "3") (pinfunction "3_3") (pintype "passive"))
      (node (ref "SV6") (pin "2") (pinfunction "2_2") (pintype "passive"))
    )
    (net (code "50") (name "Net-(PDIO8-C)") (class "Default")
      (node (ref "PDIO8") (pin "K") (pinfunction "C_K") (pintype "passive"))
      (node (ref "RN2") (pin "2") (pinfunction "2_2") (pintype "passive"))
      (node (ref "SV6") (pin "1") (pinfunction "1_1") (pintype "passive"))
    )
    (net (code "51") (name "Net-(R6-PadS)") (class "Default")
      (node (ref "R6") (pin "S") (pinfunction "S_S") (pintype "passive"))
      (node (ref "SV4") (pin "3") (pinfunction "3_3") (pintype "passive"))
    )
    (net (code "52") (name "Net-(RN1-Pad1)") (class "Default")
      (node (ref "RN1") (pin "1") (pinfunction "1_1") (pintype "passive"))
      (node (ref "RN2") (pin "1") (pinfunction "1_1") (pintype "passive"))
      (node (ref "SV6") (pin "10") (pinfunction "10_10") (pintype "passive"))
    )
    (net (code "53") (name "Net-(RT1-Pad1)") (class "Default")
      (node (ref "RT1") (pin "1") (pinfunction "1_1") (pintype "passive"))
      (node (ref "RT3") (pin "2") (pinfunction "2_2") (pintype "passive"))
      (node (ref "TR1") (pin "G") (pinfunction "G_G") (pintype "passive"))
      (node (ref "TW1") (pin "G") (pinfunction "G_G") (pintype "passive"))
      (node (ref "TY1") (pin "C") (pinfunction "C_C") (pintype "passive"))
    )
    (net (code "54") (name "Net-(RT2-Pad2)") (class "Default")
      (node (ref "RT2") (pin "2") (pinfunction "2_2") (pintype "passive"))
      (node (ref "RT4") (pin "2") (pinfunction "2_2") (pintype "passive"))
      (node (ref "TR2") (pin "G") (pinfunction "G_G") (pintype "passive"))
      (node (ref "TW2") (pin "G") (pinfunction "G_G") (pintype "passive"))
      (node (ref "TY2") (pin "C") (pinfunction "C_C") (pintype "passive"))
    )
    (net (code "55") (name "Net-(RT5-Pad2)") (class "Default")
      (node (ref "RT5") (pin "2") (pinfunction "2_2") (pintype "passive"))
      (node (ref "TY1") (pin "B") (pinfunction "B_B") (pintype "passive"))
    )
    (net (code "56") (name "Net-(RT6-Pad1)") (class "Default")
      (node (ref "RT6") (pin "1") (pinfunction "1_1") (pintype "passive"))
      (node (ref "TY2") (pin "B") (pinfunction "B_B") (pintype "passive"))
    )
    (net (code "57") (name "Net-(RW1-Pad1)") (class "Default")
      (node (ref "RW1") (pin "1") (pinfunction "1_1") (pintype "passive"))
      (node (ref "RW3") (pin "2") (pinfunction "2_2") (pintype "passive"))
      (node (ref "TR3") (pin "G") (pinfunction "G_G") (pintype "passive"))
      (node (ref "TW3") (pin "G") (pinfunction "G_G") (pintype "passive"))
      (node (ref "TY3") (pin "C") (pinfunction "C_C") (pintype "passive"))
    )
    (net (code "58") (name "Net-(RW2-Pad2)") (class "Default")
      (node (ref "RW2") (pin "2") (pinfunction "2_2") (pintype "passive"))
      (node (ref "RW4") (pin "2") (pinfunction "2_2") (pintype "passive"))
      (node (ref "TR4") (pin "G") (pinfunction "G_G") (pintype "passive"))
      (node (ref "TW4") (pin "G") (pinfunction "G_G") (pintype "passive"))
      (node (ref "TY4") (pin "C") (pinfunction "C_C") (pintype "passive"))
    )
    (net (code "59") (name "Net-(RW5-Pad2)") (class "Default")
      (node (ref "RW5") (pin "2") (pinfunction "2_2") (pintype "passive"))
      (node (ref "TY3") (pin "B") (pinfunction "B_B") (pintype "passive"))
    )
    (net (code "60") (name "Net-(RW6-Pad1)") (class "Default")
      (node (ref "RW6") (pin "1") (pinfunction "1_1") (pintype "passive"))
      (node (ref "TY4") (pin "B") (pinfunction "B_B") (pintype "passive"))
    )
    (net (code "61") (name "Net-(S1-S)") (class "Default")
      (node (ref "JP3") (pin "1") (pinfunction "1_1") (pintype "passive"))
      (node (ref "R10") (pin "1") (pinfunction "1_1") (pintype "passive"))
      (node (ref "S1") (pin "1") (pinfunction "S_1") (pintype "passive"))
      (node (ref "S1") (pin "2") (pinfunction "S1_2") (pintype "passive"))
    )
    (net (code "62") (name "Net-(S2A-S)") (class "Default")
      (node (ref "S2") (pin "3") (pinfunction "S_3") (pintype "passive"))
      (node (ref "S8") (pin "3") (pinfunction "S_3") (pintype "passive"))
    )
    (net (code "63") (name "Net-(S4-S)") (class "Default")
      (node (ref "JP3") (pin "2") (pinfunction "2_2") (pintype "passive"))
      (node (ref "R9") (pin "1") (pinfunction "1_1") (pintype "passive"))
      (node (ref "S4") (pin "1") (pinfunction "S_1") (pintype "passive"))
      (node (ref "S4") (pin "2") (pinfunction "S1_2") (pintype "passive"))
    )
    (net (code "64") (name "Net-(S5-S)") (class "Default")
      (node (ref "JP3") (pin "12") (pinfunction "12_12") (pintype "passive"))
      (node (ref "R1") (pin "1") (pinfunction "1_1") (pintype "passive"))
      (node (ref "S5") (pin "1") (pinfunction "S_1") (pintype "passive"))
      (node (ref "S5") (pin "2") (pinfunction "S1_2") (pintype "passive"))
    )
    (net (code "65") (name "Net-(S6-S)") (class "Default")
      (node (ref "JP3") (pin "11") (pinfunction "11_11") (pintype "passive"))
      (node (ref "R8") (pin "1") (pinfunction "1_1") (pintype "passive"))
      (node (ref "S6") (pin "1") (pinfunction "S_1") (pintype "passive"))
      (node (ref "S6") (pin "2") (pinfunction "S1_2") (pintype "passive"))
    )
    (net (code "66") (name "Net-(S7A-S)") (class "Default")
      (node (ref "D5") (pin "C") (pinfunction "C_C") (pintype "passive"))
      (node (ref "D7") (pin "C") (pinfunction "C_C") (pintype "passive"))
      (node (ref "RW1") (pin "2") (pinfunction "2_2") (pintype "passive"))
      (node (ref "RW2") (pin "1") (pinfunction "1_1") (pintype "passive"))
      (node (ref "RW7") (pin "2") (pinfunction "2_2") (pintype "passive"))
      (node (ref "S7") (pin "3") (pinfunction "S_3") (pintype "passive"))
      (node (ref "TR3") (pin "S") (pinfunction "S_S") (pintype "passive"))
      (node (ref "TR4") (pin "S") (pinfunction "S_S") (pintype "passive"))
    )
    (net (code "67") (name "Net-(S9A-S)") (class "Default")
      (node (ref "D1") (pin "C") (pinfunction "C_C") (pintype "passive"))
      (node (ref "D3") (pin "C") (pinfunction "C_C") (pintype "passive"))
      (node (ref "RT1") (pin "2") (pinfunction "2_2") (pintype "passive"))
      (node (ref "RT2") (pin "1") (pinfunction "1_1") (pintype "passive"))
      (node (ref "RT7") (pin "2") (pinfunction "2_2") (pintype "passive"))
      (node (ref "S9") (pin "3") (pinfunction "S_3") (pintype "passive"))
      (node (ref "TR1") (pin "S") (pinfunction "S_S") (pintype "passive"))
      (node (ref "TR2") (pin "S") (pinfunction "S_S") (pintype "passive"))
    )
    (net (code "68") (name "unconnected-(J2-Pad2)") (class "Default")
      (node (ref "J2") (pin "2") (pinfunction "2_2") (pintype "passive"))
    )
    (net (code "69") (name "unconnected-(JP3-Pad3)") (class "Default")
      (node (ref "JP3") (pin "3") (pinfunction "3_3") (pintype "passive"))
    )
    (net (code "70") (name "unconnected-(JP3-Pad4)") (class "Default")
      (node (ref "JP3") (pin "4") (pinfunction "4_4") (pintype "passive"))
    )
    (net (code "71") (name "unconnected-(JP4-Pad1)") (class "Default")
      (node (ref "JP4") (pin "1") (pinfunction "1_1") (pintype "passive"))
    )
    (net (code "72") (name "unconnected-(JP4-Pad3)") (class "Default")
      (node (ref "JP4") (pin "3") (pinfunction "3_3") (pintype "passive"))
    )
    (net (code "73") (name "unconnected-(JP4-Pad13)") (class "Default")
      (node (ref "JP4") (pin "13") (pinfunction "13_13") (pintype "passive"))
    )
    (net (code "74") (name "unconnected-(JP4-Pad14)") (class "Default")
      (node (ref "JP4") (pin "14") (pinfunction "14_14") (pintype "passive"))
    )
    (net (code "75") (name "unconnected-(S2A-O-Pad1)") (class "Default")
      (node (ref "S2") (pin "1") (pinfunction "O_1") (pintype "passive"))
    )
    (net (code "76") (name "unconnected-(S7A-O-Pad1)") (class "Default")
      (node (ref "S7") (pin "1") (pinfunction "O_1") (pintype "passive"))
    )
    (net (code "77") (name "unconnected-(S8A-O-Pad1)") (class "Default")
      (node (ref "S8") (pin "1") (pinfunction "O_1") (pintype "passive"))
    )
    (net (code "78") (name "unconnected-(S9A-O-Pad1)") (class "Default")
      (node (ref "S9") (pin "1") (pinfunction "O_1") (pintype "passive"))
    )
    (net (code "79") (name "unconnected-(SV3-Pad2)") (class "Default")
      (node (ref "SV3") (pin "2") (pinfunction "2_2") (pintype "passive"))
    )
    (net (code "80") (name "unconnected-(SV4-Pad7)") (class "Default")
      (node (ref "SV4") (pin "7") (pinfunction "7_7") (pintype "passive"))
    )
    (net (code "81") (name "unconnected-(SV4-Pad8)") (class "Default")
      (node (ref "SV4") (pin "8") (pinfunction "8_8") (pintype "passive"))
    )
    (net (code "82") (name "unconnected-(SV5-Pad1)") (class "Default")
      (node (ref "SV5") (pin "1") (pinfunction "1_1") (pintype "passive"))
    )
    (net (code "83") (name "unconnected-(SV5-Pad2)") (class "Default")
      (node (ref "SV5") (pin "2") (pinfunction "2_2") (pintype "passive"))
    )
  )
)
